# Power.net
KiCad netlist of a schematic drawn in Altium Designer
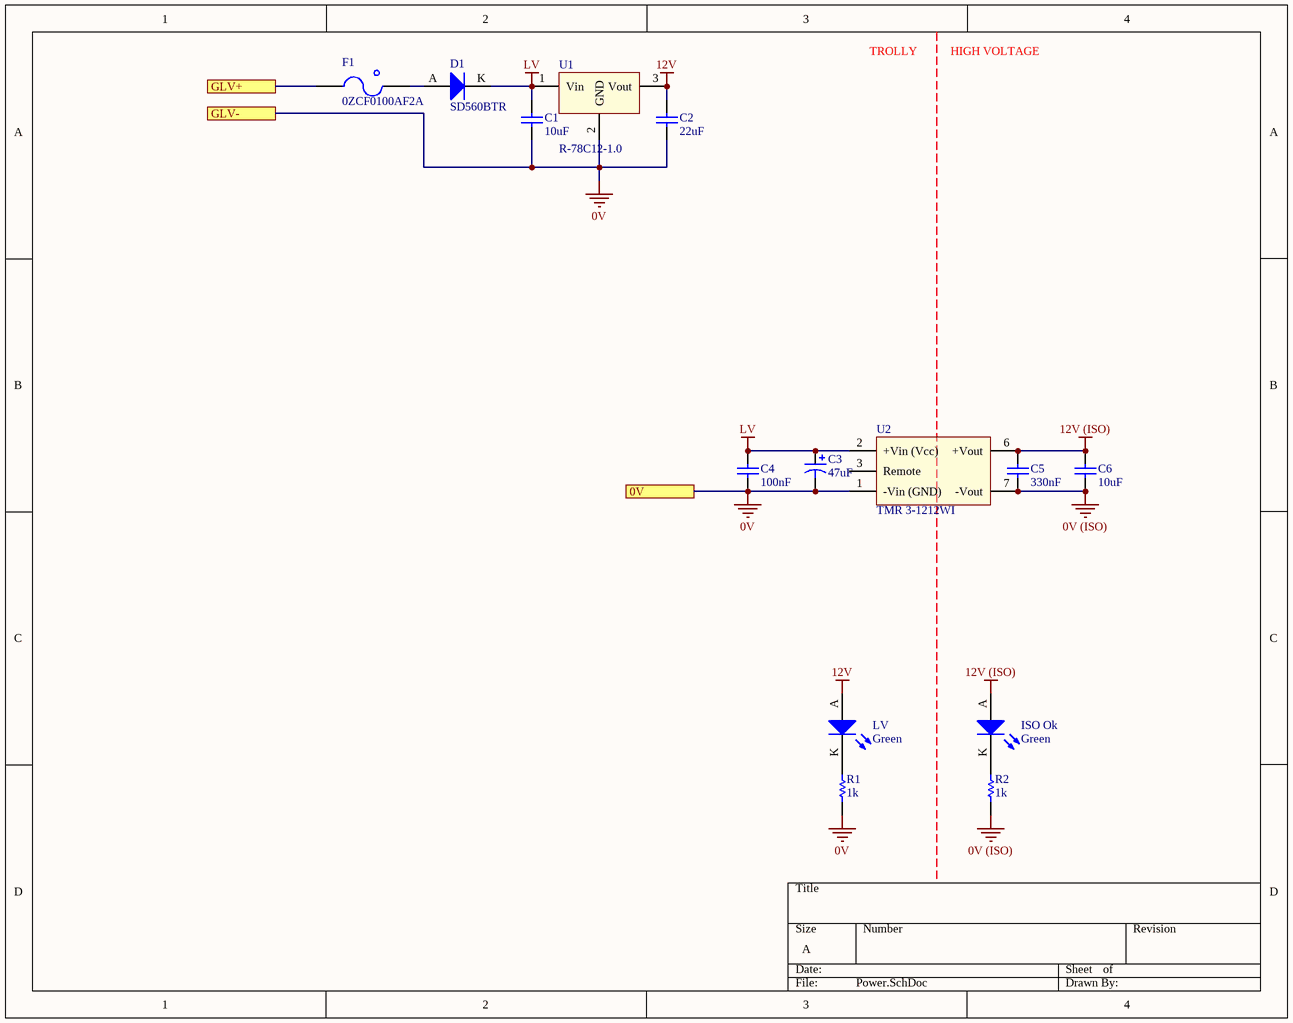
[diagram p0: Power.SchDoc]

(export (version "E")
  (design (tool "Eeschema 10.0.6"))
  (components
    (comp (ref "C1")
      (value "10uF")
      (footprint "0805")
      (fields
        (field (name "PART NUMBER") "GRM21BR6YA106KE43L")
        (field (name "TOLERANCE") "10%")
        (field (name "MANUFACTURER") "muRata")
      )
      (libsource (lib "ts_20-standard-library") (part "Capacitor"))
    )
    (comp (ref "C2")
      (value "22uF")
      (footprint "1206")
      (fields
        (field (name "PART NUMBER") "CC1206MKX5R7BB226")
        (field (name "TOLERANCE") "20%")
        (field (name "MANUFACTURER") "YAGEO")
      )
      (libsource (lib "ts_20-standard-library") (part "Capacitor"))
    )
    (comp (ref "C3")
      (value "~")
      (footprint "2924")
      (fields
        (field (name "PART NUMBER") "TAJV476K035RNJ")
        (field (name "TOLERANCE") "10%")
        (field (name "MANUFACTURER") "AVX Corporation")
      )
      (libsource (lib "ts_20-standard-library") (part "Capacitor (Polarised)"))
    )
    (comp (ref "C4")
      (value "100nF")
      (footprint "0805")
      (fields
        (field (name "PART NUMBER") "GCM21BR71H104KA37L")
        (field (name "TOLERANCE") "±10%")
        (field (name "MANUFACTURER") "muRata")
      )
      (libsource (lib "ts_20-standard-library") (part "Capacitor"))
    )
    (comp (ref "C5")
      (value "330nF")
      (footprint "0805")
      (fields
        (field (name "PART NUMBER") "GCM219R71H334KA55D")
        (field (name "TOLERANCE") "±10%")
        (field (name "MANUFACTURER") "muRata")
      )
      (libsource (lib "ts_20-standard-library") (part "Capacitor"))
    )
    (comp (ref "C6")
      (value "10uF")
      (footprint "0805")
      (fields
        (field (name "PART NUMBER") "GRM21BR6YA106KE43L")
        (field (name "TOLERANCE") "10%")
        (field (name "MANUFACTURER") "muRata")
      )
      (libsource (lib "ts_20-standard-library") (part "Capacitor"))
    )
    (comp (ref "D1")
      (value "SD560BTR")
      (footprint "SMB Diode")
      (description "1.2V_F 600V 5A SMB")
      (fields
        (field (name "MANUFACTURER") "SMC Diode Solutions")
        (field (name "DIGIKEY PART NUMBER") "1655-1530-2-ND")
      )
      (libsource (lib "ts_20-standard-library") (part "Diode"))
    )
    (comp (ref "F1")
      (value "0ZCF0100AF2A")
      (footprint "2920")
      (description "PTC RESET FUSE 60V 1A 292")
      (fields
        (field (name "MANUFACTURER") "Littelfuse Inc.")
        (field (name "DIGIKEY PART NUMBER") "507-2070-1-ND")
      )
      (libsource (lib "ts_20-standard-library") (part "PTC Fuse"))
    )
    (comp (ref "ISO Ok")
      (value "Green")
      (footprint "0805 LED")
      (description "Green LED Indication - Discrete 1.75V 0805 (2012 Metric)")
      (fields (field (name "PART NUMBER") "SML-210FTT86") (field (name "MANUFACTURER") "ROHM Semiconductor"))
      (libsource (lib "ts_20-standard-library") (part "LED"))
    )
    (comp (ref "LV")
      (value "Green")
      (footprint "0805 LED")
      (description "Green LED Indication - Discrete 1.75V 0805 (2012 Metric)")
      (fields (field (name "PART NUMBER") "SML-210FTT86") (field (name "MANUFACTURER") "ROHM Semiconductor"))
      (libsource (lib "ts_20-standard-library") (part "LED"))
    )
    (comp (ref "R1")
      (value "1k")
      (footprint "0805")
      (fields
        (field (name "PART NUMBER") "RC0805FR071KL")
        (field (name "MANUFACTURER") "YAGEO")
        (field (name "TOLERANCE") "0.01")
      )
      (libsource (lib "ts_20-standard-library") (part "Resistor"))
    )
    (comp (ref "R2")
      (value "1k")
      (footprint "0805")
      (fields
        (field (name "PART NUMBER") "RC0805FR071KL")
        (field (name "MANUFACTURER") "YAGEO")
        (field (name "TOLERANCE") "0.01")
      )
      (libsource (lib "ts_20-standard-library") (part "Resistor"))
    )
    (comp (ref "U1")
      (value "R-78C12-1.0")
      (footprint "RECOM 3-SIP")
      (description "3PIN DC DC CONVERTER 12V 12W")
      (fields (field (name "MANUFACTURER") "Recom") (field (name "DIGIKEY PART NUMBER") "945-1392-5-ND"))
      (libsource (lib "ts_20-standard-library") (part "R-78C12-1.0"))
    )
    (comp (ref "U2")
      (value "TMR 3-1212WI")
      (footprint "TRECO 8-SIP")
      (description "DC DC CONVERTER 12V 3W")
      (fields (field (name "MANUFACTURER") "Traco Power") (field (name "DIGIKEY PART NUMBER") "1951-2367-ND"))
      (libsource (lib "ts_20-standard-library") (part "TMR 3-1212WI"))
    )
  )
  (nets
    (net (code "1") (name "/GLV+") (class "Default")
      (node (ref "F1") (pin "1") (pinfunction "1_1") (pintype "passive"))
    )
    (net (code "2") (name "0V") (class "Default")
      (node (ref "C1") (pin "1") (pinfunction "1_1") (pintype "passive"))
      (node (ref "C2") (pin "1") (pinfunction "1_1") (pintype "passive"))
      (node (ref "C3") (pin "1") (pinfunction "1_1") (pintype "passive"))
      (node (ref "C4") (pin "1") (pinfunction "1_1") (pintype "passive"))
      (node (ref "R1") (pin "1") (pinfunction "1_1") (pintype "passive"))
      (node (ref "U1") (pin "2") (pinfunction "GND_2") (pintype "passive"))
      (node (ref "U2") (pin "1") (pinfunction "-Vin_(GND)_1") (pintype "passive"))
    )
    (net (code "3") (name "0V (ISO)") (class "Default")
      (node (ref "C5") (pin "1") (pinfunction "1_1") (pintype "passive"))
      (node (ref "C6") (pin "1") (pinfunction "1_1") (pintype "passive"))
      (node (ref "R2") (pin "1") (pinfunction "1_1") (pintype "passive"))
      (node (ref "U2") (pin "7") (pinfunction "-Vout_7") (pintype "passive"))
    )
    (net (code "4") (name "12V") (class "Default")
      (node (ref "C2") (pin "2") (pinfunction "2_2") (pintype "passive"))
      (node (ref "LV") (pin "A") (pinfunction "A_A") (pintype "passive"))
      (node (ref "U1") (pin "3") (pinfunction "Vout_3") (pintype "passive"))
    )
    (net (code "5") (name "12V (ISO)") (class "Default")
      (node (ref "C5") (pin "2") (pinfunction "2_2") (pintype "passive"))
      (node (ref "C6") (pin "2") (pinfunction "2_2") (pintype "passive"))
      (node (ref "ISO Ok") (pin "A") (pinfunction "A_A") (pintype "passive"))
      (node (ref "U2") (pin "6") (pinfunction "+Vout_6") (pintype "passive"))
    )
    (net (code "6") (name "LV") (class "Default")
      (node (ref "C1") (pin "2") (pinfunction "2_2") (pintype "passive"))
      (node (ref "C3") (pin "2") (pinfunction "2_2") (pintype "passive"))
      (node (ref "C4") (pin "2") (pinfunction "2_2") (pintype "passive"))
      (node (ref "D1") (pin "K") (pinfunction "K_K") (pintype "passive"))
      (node (ref "U1") (pin "1") (pinfunction "Vin_1") (pintype "passive"))
      (node (ref "U2") (pin "2") (pinfunction "+Vin_(Vcc)_2") (pintype "passive"))
    )
    (net (code "7") (name "Net-(D1-PadA)") (class "Default")
      (node (ref "D1") (pin "A") (pinfunction "A_A") (pintype "passive"))
      (node (ref "F1") (pin "2") (pinfunction "2_2") (pintype "passive"))
    )
    (net (code "8") (name "Net-(ISO Ok-PadK)") (class "Default")
      (node (ref "ISO Ok") (pin "K") (pinfunction "K_K") (pintype "passive"))
      (node (ref "R2") (pin "2") (pinfunction "2_2") (pintype "passive"))
    )
    (net (code "9") (name "Net-(LV-PadK)") (class "Default")
      (node (ref "LV") (pin "K") (pinfunction "K_K") (pintype "passive"))
      (node (ref "R1") (pin "2") (pinfunction "2_2") (pintype "passive"))
    )
    (net (code "10") (name "unconnected-(U2-Remote-Pad3)") (class "Default")
      (node (ref "U2") (pin "3") (pinfunction "Remote_3") (pintype "passive"))
    )
  )
)
